# Sheet6.net
KiCad netlist of a schematic drawn in Altium Designer
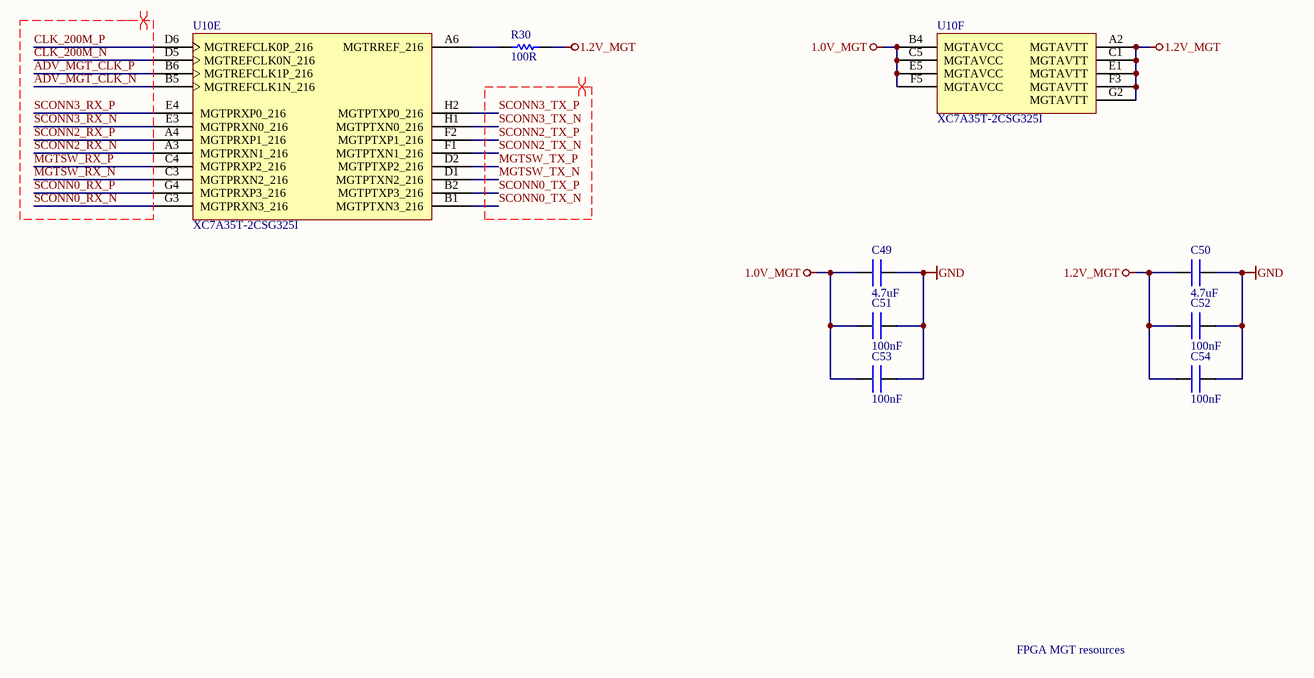
[diagram p0: Sheet6.SchDoc]

(export (version "E")
  (design (tool "Eeschema 10.0.6"))
  (components
    (comp (ref "C49")
      (value "4.7uF")
      (footprint "CAPC1608X08N")
      (description "Ceramic Chip Capacitor")
      (libsource (lib "Integrated_Library") (part "C0603"))
    )
    (comp (ref "C50")
      (value "4.7uF")
      (footprint "CAPC1608X08N")
      (description "Ceramic Chip Capacitor")
      (libsource (lib "Integrated_Library") (part "C0603"))
    )
    (comp (ref "C51")
      (value "100nF")
      (footprint "CAPC1005X05L")
      (description "Ceramic Chip Capacitor")
      (libsource (lib "Integrated_Library") (part "C0402"))
    )
    (comp (ref "C52")
      (value "100nF")
      (footprint "CAPC1005X05L")
      (description "Ceramic Chip Capacitor")
      (libsource (lib "Integrated_Library") (part "C0402"))
    )
    (comp (ref "C53")
      (value "100nF")
      (footprint "CAPC1005X05L")
      (description "Ceramic Chip Capacitor")
      (libsource (lib "Integrated_Library") (part "C0402"))
    )
    (comp (ref "C54")
      (value "100nF")
      (footprint "CAPC1005X05L")
      (description "Ceramic Chip Capacitor")
      (libsource (lib "Integrated_Library") (part "C0402"))
    )
    (comp (ref "R30")
      (value "100R")
      (footprint "RESC1005X05N")
      (description "Ceramic Chip Resistor")
      (libsource (lib "Integrated_Library") (part "R0402"))
    )
    (comp (ref "U10")
      (value "XC7A35T-2CSG325I")
      (footprint "XC7A35T-2CSG325I")
      (description "Artix-7 FPGA, 150 User I/Os, 4 GTP, 324-Ball BGA, Speed Grade 2, Industrial Grade, Pb-Free")
      (fields (field (name "MANUFACTURER") "Xilinx"))
      (libsource (lib "Integrated_Library") (part "XC7A35T-2CSG325I"))
    )
  )
  (nets
    (net (code "1") (name "/ADV_MGT_CLK_N") (class "Default")
      (node (ref "U10") (pin "B5") (pinfunction "MGTREFCLK1N_216_B5") (pintype "input"))
    )
    (net (code "2") (name "/ADV_MGT_CLK_P") (class "Default")
      (node (ref "U10") (pin "B6") (pinfunction "MGTREFCLK1P_216_B6") (pintype "input"))
    )
    (net (code "3") (name "/CLK_200M_N") (class "Default")
      (node (ref "U10") (pin "D5") (pinfunction "MGTREFCLK0N_216_D5") (pintype "input"))
    )
    (net (code "4") (name "/CLK_200M_P") (class "Default")
      (node (ref "U10") (pin "D6") (pinfunction "MGTREFCLK0P_216_D6") (pintype "input"))
    )
    (net (code "5") (name "/MGTSW_RX_N") (class "Default")
      (node (ref "U10") (pin "C3") (pinfunction "MGTPRXN2_216_C3") (pintype "input"))
    )
    (net (code "6") (name "/MGTSW_RX_P") (class "Default")
      (node (ref "U10") (pin "C4") (pinfunction "MGTPRXP2_216_C4") (pintype "input"))
    )
    (net (code "7") (name "/MGTSW_TX_N") (class "Default")
      (node (ref "U10") (pin "D1") (pinfunction "MGTPTXN2_216_D1") (pintype "output"))
    )
    (net (code "8") (name "/MGTSW_TX_P") (class "Default")
      (node (ref "U10") (pin "D2") (pinfunction "MGTPTXP2_216_D2") (pintype "output"))
    )
    (net (code "9") (name "/SCONN0_RX_N") (class "Default")
      (node (ref "U10") (pin "G3") (pinfunction "MGTPRXN3_216_G3") (pintype "input"))
    )
    (net (code "10") (name "/SCONN0_RX_P") (class "Default")
      (node (ref "U10") (pin "G4") (pinfunction "MGTPRXP3_216_G4") (pintype "input"))
    )
    (net (code "11") (name "/SCONN0_TX_N") (class "Default")
      (node (ref "U10") (pin "B1") (pinfunction "MGTPTXN3_216_B1") (pintype "output"))
    )
    (net (code "12") (name "/SCONN0_TX_P") (class "Default")
      (node (ref "U10") (pin "B2") (pinfunction "MGTPTXP3_216_B2") (pintype "output"))
    )
    (net (code "13") (name "/SCONN2_RX_N") (class "Default")
      (node (ref "U10") (pin "A3") (pinfunction "MGTPRXN1_216_A3") (pintype "input"))
    )
    (net (code "14") (name "/SCONN2_RX_P") (class "Default")
      (node (ref "U10") (pin "A4") (pinfunction "MGTPRXP1_216_A4") (pintype "input"))
    )
    (net (code "15") (name "/SCONN2_TX_N") (class "Default")
      (node (ref "U10") (pin "F1") (pinfunction "MGTPTXN1_216_F1") (pintype "output"))
    )
    (net (code "16") (name "/SCONN2_TX_P") (class "Default")
      (node (ref "U10") (pin "F2") (pinfunction "MGTPTXP1_216_F2") (pintype "output"))
    )
    (net (code "17") (name "/SCONN3_RX_N") (class "Default")
      (node (ref "U10") (pin "E3") (pinfunction "MGTPRXN0_216_E3") (pintype "input"))
    )
    (net (code "18") (name "/SCONN3_RX_P") (class "Default")
      (node (ref "U10") (pin "E4") (pinfunction "MGTPRXP0_216_E4") (pintype "input"))
    )
    (net (code "19") (name "/SCONN3_TX_N") (class "Default")
      (node (ref "U10") (pin "H1") (pinfunction "MGTPTXN0_216_H1") (pintype "output"))
    )
    (net (code "20") (name "/SCONN3_TX_P") (class "Default")
      (node (ref "U10") (pin "H2") (pinfunction "MGTPTXP0_216_H2") (pintype "output"))
    )
    (net (code "21") (name "1.0V_MGT") (class "Default")
      (node (ref "C49") (pin "2") (pinfunction "2_2") (pintype "passive"))
      (node (ref "C51") (pin "2") (pinfunction "2_2") (pintype "passive"))
      (node (ref "C53") (pin "2") (pinfunction "2_2") (pintype "passive"))
      (node (ref "U10") (pin "B4") (pinfunction "MGTAVCC_B4") (pintype "power_in"))
      (node (ref "U10") (pin "C5") (pinfunction "MGTAVCC_C5") (pintype "power_in"))
      (node (ref "U10") (pin "E5") (pinfunction "MGTAVCC_E5") (pintype "power_in"))
      (node (ref "U10") (pin "F5") (pinfunction "MGTAVCC_F5") (pintype "power_in"))
    )
    (net (code "22") (name "1.2V_MGT") (class "Default")
      (node (ref "C50") (pin "2") (pinfunction "2_2") (pintype "passive"))
      (node (ref "C52") (pin "2") (pinfunction "2_2") (pintype "passive"))
      (node (ref "C54") (pin "2") (pinfunction "2_2") (pintype "passive"))
      (node (ref "R30") (pin "1") (pinfunction "1_1") (pintype "passive"))
      (node (ref "U10") (pin "A2") (pinfunction "MGTAVTT_A2") (pintype "power_in"))
      (node (ref "U10") (pin "C1") (pinfunction "MGTAVTT_C1") (pintype "power_in"))
      (node (ref "U10") (pin "E1") (pinfunction "MGTAVTT_E1") (pintype "power_in"))
      (node (ref "U10") (pin "F3") (pinfunction "MGTAVTT_F3") (pintype "power_in"))
      (node (ref "U10") (pin "G2") (pinfunction "MGTAVTT_G2") (pintype "power_in"))
    )
    (net (code "23") (name "GND") (class "Default")
      (node (ref "C49") (pin "1") (pinfunction "1_1") (pintype "passive"))
      (node (ref "C50") (pin "1") (pinfunction "1_1") (pintype "passive"))
      (node (ref "C51") (pin "1") (pinfunction "1_1") (pintype "passive"))
      (node (ref "C52") (pin "1") (pinfunction "1_1") (pintype "passive"))
      (node (ref "C53") (pin "1") (pinfunction "1_1") (pintype "passive"))
      (node (ref "C54") (pin "1") (pinfunction "1_1") (pintype "passive"))
    )
    (net (code "24") (name "Net-(U10E-MGTRREF_216)") (class "Default")
      (node (ref "R30") (pin "2") (pinfunction "2_2") (pintype "passive"))
      (node (ref "U10") (pin "A6") (pinfunction "MGTRREF_216_A6") (pintype "input"))
    )
  )
)
